# IR4427.net
KiCad netlist of a schematic drawn in EAGLE
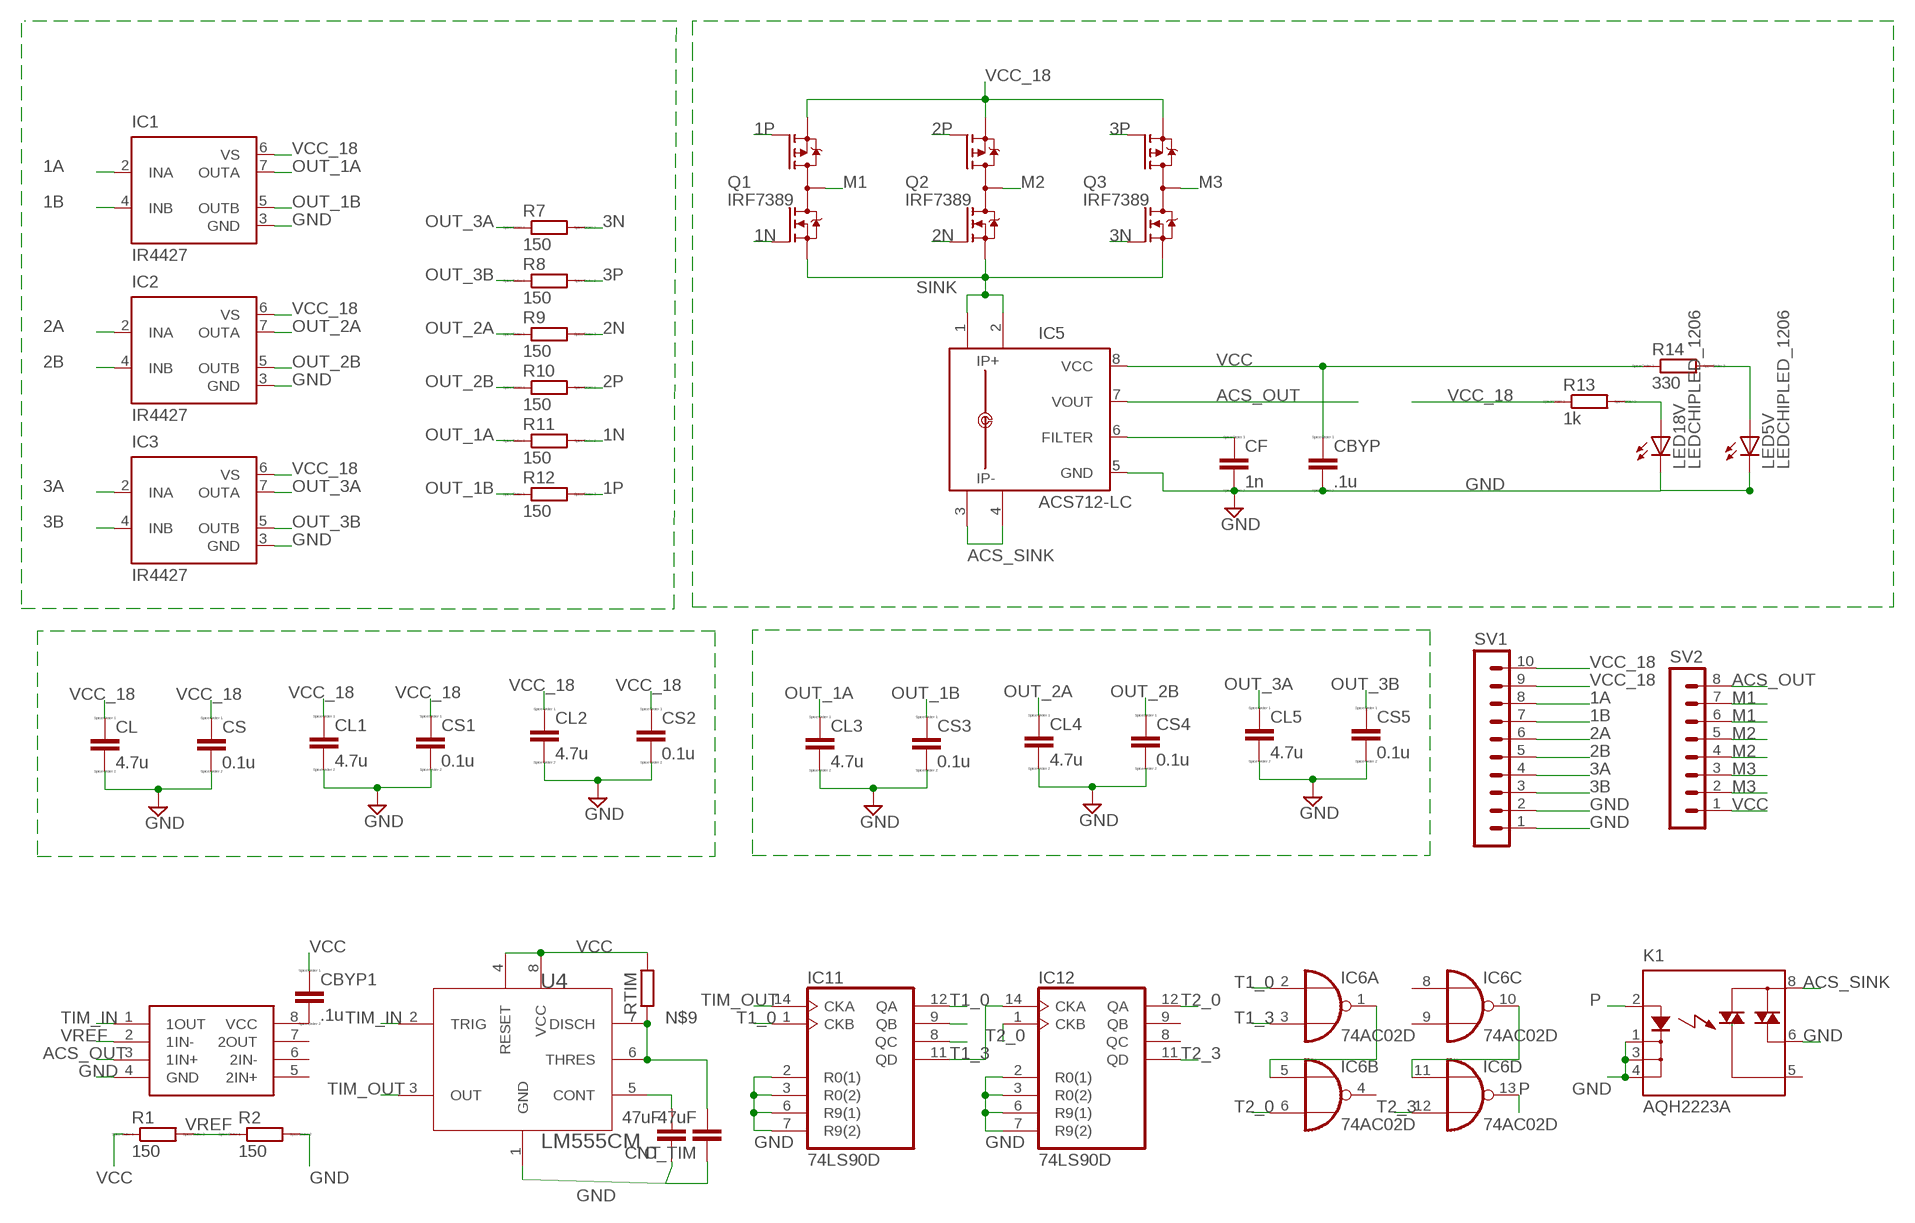
[diagram p0: schematic, sheet 1]

(export (version "E")
  (design (tool "Eeschema 10.0.6"))
  (components
    (comp (ref "CBYP")
      (value ".1u")
      (footprint "eagle-import:C1206")
      (libsource (lib "eagle-import") (part "CC1206"))
    )
    (comp (ref "CBYP1")
      (value ".1u")
      (footprint "eagle-import:C1206")
      (libsource (lib "eagle-import") (part "CC1206"))
    )
    (comp (ref "CF")
      (value "1n")
      (footprint "eagle-import:C1206")
      (libsource (lib "eagle-import") (part "CC1206"))
    )
    (comp (ref "CL")
      (value "4.7u")
      (footprint "eagle-import:C1206")
      (libsource (lib "eagle-import") (part "CC1206"))
    )
    (comp (ref "CL1")
      (value "4.7u")
      (footprint "eagle-import:C1206")
      (libsource (lib "eagle-import") (part "CC1206"))
    )
    (comp (ref "CL2")
      (value "4.7u")
      (footprint "eagle-import:C1206")
      (libsource (lib "eagle-import") (part "CC1206"))
    )
    (comp (ref "CL3")
      (value "4.7u")
      (footprint "eagle-import:C1206")
      (libsource (lib "eagle-import") (part "CC1206"))
    )
    (comp (ref "CL4")
      (value "4.7u")
      (footprint "eagle-import:C1206")
      (libsource (lib "eagle-import") (part "CC1206"))
    )
    (comp (ref "CL5")
      (value "4.7u")
      (footprint "eagle-import:C1206")
      (libsource (lib "eagle-import") (part "CC1206"))
    )
    (comp (ref "CNT")
      (value "47uF")
      (footprint "eagle-import:C1206")
      (libsource (lib "eagle-import") (part "C-EUC1206"))
    )
    (comp (ref "CS")
      (value "0.1u")
      (footprint "eagle-import:C1206")
      (libsource (lib "eagle-import") (part "CC1206"))
    )
    (comp (ref "CS1")
      (value "0.1u")
      (footprint "eagle-import:C1206")
      (libsource (lib "eagle-import") (part "CC1206"))
    )
    (comp (ref "CS2")
      (value "0.1u")
      (footprint "eagle-import:C1206")
      (libsource (lib "eagle-import") (part "CC1206"))
    )
    (comp (ref "CS3")
      (value "0.1u")
      (footprint "eagle-import:C1206")
      (libsource (lib "eagle-import") (part "CC1206"))
    )
    (comp (ref "CS4")
      (value "0.1u")
      (footprint "eagle-import:C1206")
      (libsource (lib "eagle-import") (part "CC1206"))
    )
    (comp (ref "CS5")
      (value "0.1u")
      (footprint "eagle-import:C1206")
      (libsource (lib "eagle-import") (part "CC1206"))
    )
    (comp (ref "C_TIM")
      (value "47uF")
      (footprint "eagle-import:C1206")
      (libsource (lib "eagle-import") (part "C-EUC1206"))
    )
    (comp (ref "IC1")
      (value "IR4427")
      (footprint "eagle-import:DIL08")
      (fields (field (name "MF") "INTERNATIONAL RECTIFIER(IR)"))
      (libsource (lib "eagle-import") (part "IR4427"))
    )
    (comp (ref "IC2")
      (value "IR4427")
      (footprint "eagle-import:DIL08")
      (fields (field (name "MF") "INTERNATIONAL RECTIFIER(IR)"))
      (libsource (lib "eagle-import") (part "IR4427"))
    )
    (comp (ref "IC3")
      (value "IR4427")
      (footprint "eagle-import:DIL08")
      (fields (field (name "MF") "INTERNATIONAL RECTIFIER(IR)"))
      (libsource (lib "eagle-import") (part "IR4427"))
    )
    (comp (ref "IC5")
      (value "ACS712-LC")
      (footprint "eagle-import:SOIC8")
      (libsource (lib "eagle-import") (part "ACS712-LC"))
    )
    (comp (ref "IC6")
      (value "74AC02D")
      (footprint "eagle-import:SO14")
      (libsource (lib "eagle-import") (part "7402DAC"))
    )
    (comp (ref "IC11")
      (value "74LS90D")
      (footprint "eagle-import:SO14")
      (libsource (lib "eagle-import") (part "7490DLS"))
    )
    (comp (ref "IC12")
      (value "74LS90D")
      (footprint "eagle-import:SO14")
      (libsource (lib "eagle-import") (part "7490DLS"))
    )
    (comp (ref "K1")
      (value "AQH2223A")
      (footprint "eagle-import:DIL07SMD")
      (fields (field (name "MF") "AROMAT/ MATSUSHITA"))
      (libsource (lib "eagle-import") (part "AQH223A2"))
    )
    (comp (ref "LED5V")
      (value "LEDCHIPLED_1206")
      (footprint "eagle-import:CHIPLED_1206")
      (libsource (lib "eagle-import") (part "LEDCHIPLED_1206"))
    )
    (comp (ref "LED18V")
      (value "LEDCHIPLED_1206")
      (footprint "eagle-import:CHIPLED_1206")
      (libsource (lib "eagle-import") (part "LEDCHIPLED_1206"))
    )
    (comp (ref "Q1")
      (value "IRF7389")
      (footprint "eagle-import:SO08-IRF")
      (libsource (lib "eagle-import") (part "IRF7389"))
    )
    (comp (ref "Q2")
      (value "IRF7389")
      (footprint "eagle-import:SO08-IRF")
      (libsource (lib "eagle-import") (part "IRF7389"))
    )
    (comp (ref "Q3")
      (value "IRF7389")
      (footprint "eagle-import:SO08-IRF")
      (libsource (lib "eagle-import") (part "IRF7389"))
    )
    (comp (ref "R1")
      (value "150")
      (footprint "eagle-import:R1206")
      (libsource (lib "eagle-import") (part "RR1206"))
    )
    (comp (ref "R2")
      (value "150")
      (footprint "eagle-import:R1206")
      (libsource (lib "eagle-import") (part "RR1206"))
    )
    (comp (ref "R7")
      (value "150")
      (footprint "eagle-import:R1206")
      (libsource (lib "eagle-import") (part "RR1206"))
    )
    (comp (ref "R8")
      (value "150")
      (footprint "eagle-import:R1206")
      (libsource (lib "eagle-import") (part "RR1206"))
    )
    (comp (ref "R9")
      (value "150")
      (footprint "eagle-import:R1206")
      (libsource (lib "eagle-import") (part "RR1206"))
    )
    (comp (ref "R10")
      (value "150")
      (footprint "eagle-import:R1206")
      (libsource (lib "eagle-import") (part "RR1206"))
    )
    (comp (ref "R11")
      (value "150")
      (footprint "eagle-import:R1206")
      (libsource (lib "eagle-import") (part "RR1206"))
    )
    (comp (ref "R12")
      (value "150")
      (footprint "eagle-import:R1206")
      (libsource (lib "eagle-import") (part "RR1206"))
    )
    (comp (ref "R13")
      (value "1k")
      (footprint "eagle-import:R1206")
      (libsource (lib "eagle-import") (part "RR1206"))
    )
    (comp (ref "R14")
      (value "330")
      (footprint "eagle-import:R1206")
      (libsource (lib "eagle-import") (part "RR1206"))
    )
    (comp (ref "RTIM")
      (value "R-EU_R1206")
      (footprint "eagle-import:R1206")
      (libsource (lib "eagle-import") (part "R-EU_R1206"))
    )
    (comp (ref "SV1")
      (value "MA10-1")
      (footprint "eagle-import:MA10-1")
      (libsource (lib "eagle-import") (part "MA10-1"))
    )
    (comp (ref "SV2")
      (value "MA08-1")
      (footprint "eagle-import:MA08-1")
      (libsource (lib "eagle-import") (part "MA08-1"))
    )
    (comp (ref "U1")
      (value "LM293D")
      (footprint "eagle-import:8-SOIC")
      (fields
        (field (name "DIGIKEY_PART_NUMBER") "296-9531-5-ND")
        (field (name "MANUFACTURER") "Texas Instruments")
        (field (name "CREATED_BY") "PCBLayout.com")
      )
      (libsource (lib "eagle-import") (part "LM293D"))
    )
    (comp (ref "U4")
      (value "LM555CM")
      (footprint "eagle-import:SOIC-8N")
      (fields
        (field (name "DIGI-KEY_PART") "LM555CMFS-ND")
        (field (name "MANUFACTURER") "ON Semiconductor")
        (field (name "CREATED_BY") "PCBLayout.com")
      )
      (libsource (lib "eagle-import") (part "LM555CM"))
    )
  )
  (nets
    (net (code "1") (name "/1A") (class "Default")
      (node (ref "IC1") (pin "2") (pinfunction "INA_2") (pintype "input"))
      (node (ref "SV1") (pin "8") (pinfunction "8_8") (pintype "passive"))
    )
    (net (code "2") (name "/1B") (class "Default")
      (node (ref "IC1") (pin "4") (pinfunction "INB_4") (pintype "input"))
      (node (ref "SV1") (pin "7") (pinfunction "7_7") (pintype "passive"))
    )
    (net (code "3") (name "/1N") (class "Default")
      (node (ref "Q1") (pin "2") (pinfunction "N-G_2") (pintype "passive"))
      (node (ref "R11") (pin "2") (pinfunction "2_2") (pintype "passive"))
    )
    (net (code "4") (name "/1P") (class "Default")
      (node (ref "Q1") (pin "4") (pinfunction "P-G_4") (pintype "passive"))
      (node (ref "R12") (pin "2") (pinfunction "2_2") (pintype "passive"))
    )
    (net (code "5") (name "/2A") (class "Default")
      (node (ref "IC2") (pin "2") (pinfunction "INA_2") (pintype "input"))
      (node (ref "SV1") (pin "6") (pinfunction "6_6") (pintype "passive"))
    )
    (net (code "6") (name "/2B") (class "Default")
      (node (ref "IC2") (pin "4") (pinfunction "INB_4") (pintype "input"))
      (node (ref "SV1") (pin "5") (pinfunction "5_5") (pintype "passive"))
    )
    (net (code "7") (name "/2N") (class "Default")
      (node (ref "Q2") (pin "2") (pinfunction "N-G_2") (pintype "passive"))
      (node (ref "R9") (pin "2") (pinfunction "2_2") (pintype "passive"))
    )
    (net (code "8") (name "/2P") (class "Default")
      (node (ref "Q2") (pin "4") (pinfunction "P-G_4") (pintype "passive"))
      (node (ref "R10") (pin "2") (pinfunction "2_2") (pintype "passive"))
    )
    (net (code "9") (name "/3A") (class "Default")
      (node (ref "IC3") (pin "2") (pinfunction "INA_2") (pintype "input"))
      (node (ref "SV1") (pin "4") (pinfunction "4_4") (pintype "passive"))
    )
    (net (code "10") (name "/3B") (class "Default")
      (node (ref "IC3") (pin "4") (pinfunction "INB_4") (pintype "input"))
      (node (ref "SV1") (pin "3") (pinfunction "3_3") (pintype "passive"))
    )
    (net (code "11") (name "/3N") (class "Default")
      (node (ref "Q3") (pin "2") (pinfunction "N-G_2") (pintype "passive"))
      (node (ref "R7") (pin "2") (pinfunction "2_2") (pintype "passive"))
    )
    (net (code "12") (name "/3P") (class "Default")
      (node (ref "Q3") (pin "4") (pinfunction "P-G_4") (pintype "passive"))
      (node (ref "R8") (pin "2") (pinfunction "2_2") (pintype "passive"))
    )
    (net (code "13") (name "/ACS_OUT") (class "Default")
      (node (ref "IC5") (pin "7") (pinfunction "VOUT_7") (pintype "output"))
      (node (ref "SV2") (pin "8") (pinfunction "8_8") (pintype "passive"))
      (node (ref "U1") (pin "3") (pinfunction "1IN+_3") (pintype "input"))
    )
    (net (code "14") (name "/ACS_SINK") (class "Default")
      (node (ref "IC5") (pin "3") (pinfunction "IP-_3") (pintype "passive"))
      (node (ref "IC5") (pin "4") (pinfunction "IP-1_4") (pintype "passive"))
      (node (ref "K1") (pin "8") (pinfunction "DS1_8") (pintype "passive"))
    )
    (net (code "15") (name "/M1") (class "Default")
      (node (ref "Q1") (pin "5") (pinfunction "D_5") (pintype "passive"))
      (node (ref "Q1") (pin "6") (pinfunction "D_6") (pintype "passive"))
      (node (ref "Q1") (pin "7") (pinfunction "D_7") (pintype "passive"))
      (node (ref "Q1") (pin "8") (pinfunction "D_8") (pintype "passive"))
      (node (ref "SV2") (pin "6") (pinfunction "6_6") (pintype "passive"))
      (node (ref "SV2") (pin "7") (pinfunction "7_7") (pintype "passive"))
    )
    (net (code "16") (name "/M2") (class "Default")
      (node (ref "Q2") (pin "5") (pinfunction "D_5") (pintype "passive"))
      (node (ref "Q2") (pin "6") (pinfunction "D_6") (pintype "passive"))
      (node (ref "Q2") (pin "7") (pinfunction "D_7") (pintype "passive"))
      (node (ref "Q2") (pin "8") (pinfunction "D_8") (pintype "passive"))
      (node (ref "SV2") (pin "4") (pinfunction "4_4") (pintype "passive"))
      (node (ref "SV2") (pin "5") (pinfunction "5_5") (pintype "passive"))
    )
    (net (code "17") (name "/M3") (class "Default")
      (node (ref "Q3") (pin "5") (pinfunction "D_5") (pintype "passive"))
      (node (ref "Q3") (pin "6") (pinfunction "D_6") (pintype "passive"))
      (node (ref "Q3") (pin "7") (pinfunction "D_7") (pintype "passive"))
      (node (ref "Q3") (pin "8") (pinfunction "D_8") (pintype "passive"))
      (node (ref "SV2") (pin "2") (pinfunction "2_2") (pintype "passive"))
      (node (ref "SV2") (pin "3") (pinfunction "3_3") (pintype "passive"))
    )
    (net (code "18") (name "/N$9") (class "Default")
      (node (ref "RTIM") (pin "1") (pinfunction "1_1") (pintype "passive"))
      (node (ref "U4") (pin "7") (pinfunction "DISCH_7") (pintype "output"))
    )
    (net (code "19") (name "/OUT_1A") (class "Default")
      (node (ref "CL3") (pin "1") (pinfunction "1_1") (pintype "passive"))
      (node (ref "IC1") (pin "7") (pinfunction "OUTA_7") (pintype "output"))
      (node (ref "R11") (pin "1") (pinfunction "1_1") (pintype "passive"))
    )
    (net (code "20") (name "/OUT_1B") (class "Default")
      (node (ref "CS3") (pin "1") (pinfunction "1_1") (pintype "passive"))
      (node (ref "IC1") (pin "5") (pinfunction "OUTB_5") (pintype "output"))
      (node (ref "R12") (pin "1") (pinfunction "1_1") (pintype "passive"))
    )
    (net (code "21") (name "/OUT_2A") (class "Default")
      (node (ref "CL4") (pin "1") (pinfunction "1_1") (pintype "passive"))
      (node (ref "IC2") (pin "7") (pinfunction "OUTA_7") (pintype "output"))
      (node (ref "R9") (pin "1") (pinfunction "1_1") (pintype "passive"))
    )
    (net (code "22") (name "/OUT_2B") (class "Default")
      (node (ref "CS4") (pin "1") (pinfunction "1_1") (pintype "passive"))
      (node (ref "IC2") (pin "5") (pinfunction "OUTB_5") (pintype "output"))
      (node (ref "R10") (pin "1") (pinfunction "1_1") (pintype "passive"))
    )
    (net (code "23") (name "/OUT_3A") (class "Default")
      (node (ref "CL5") (pin "1") (pinfunction "1_1") (pintype "passive"))
      (node (ref "IC3") (pin "7") (pinfunction "OUTA_7") (pintype "output"))
      (node (ref "R7") (pin "1") (pinfunction "1_1") (pintype "passive"))
    )
    (net (code "24") (name "/OUT_3B") (class "Default")
      (node (ref "CS5") (pin "1") (pinfunction "1_1") (pintype "passive"))
      (node (ref "IC3") (pin "5") (pinfunction "OUTB_5") (pintype "output"))
      (node (ref "R8") (pin "1") (pinfunction "1_1") (pintype "passive"))
    )
    (net (code "25") (name "/P") (class "Default")
      (node (ref "IC6") (pin "13") (pinfunction "O_13") (pintype "output"))
      (node (ref "K1") (pin "2") (pinfunction "A_2") (pintype "passive"))
    )
    (net (code "26") (name "/SINK") (class "Default")
      (node (ref "IC5") (pin "1") (pinfunction "IP+_1") (pintype "passive"))
      (node (ref "IC5") (pin "2") (pinfunction "IP+1_2") (pintype "passive"))
      (node (ref "Q1") (pin "1") (pinfunction "N-S_1") (pintype "passive"))
      (node (ref "Q2") (pin "1") (pinfunction "N-S_1") (pintype "passive"))
      (node (ref "Q3") (pin "1") (pinfunction "N-S_1") (pintype "passive"))
    )
    (net (code "27") (name "/T1_0") (class "Default")
      (node (ref "IC11") (pin "1") (pinfunction "CKB_1") (pintype "input"))
      (node (ref "IC11") (pin "12") (pinfunction "QA_12") (pintype "output"))
      (node (ref "IC6") (pin "2") (pinfunction "I0_2") (pintype "input"))
    )
    (net (code "28") (name "/T1_3") (class "Default")
      (node (ref "IC11") (pin "11") (pinfunction "QD_11") (pintype "output"))
      (node (ref "IC12") (pin "14") (pinfunction "CKA_14") (pintype "input"))
      (node (ref "IC6") (pin "3") (pinfunction "I1_3") (pintype "input"))
    )
    (net (code "29") (name "/T2_0") (class "Default")
      (node (ref "IC12") (pin "1") (pinfunction "CKB_1") (pintype "input"))
      (node (ref "IC12") (pin "12") (pinfunction "QA_12") (pintype "output"))
      (node (ref "IC6") (pin "6") (pinfunction "I1_6") (pintype "input"))
    )
    (net (code "30") (name "/T2_3") (class "Default")
      (node (ref "IC12") (pin "11") (pinfunction "QD_11") (pintype "output"))
      (node (ref "IC6") (pin "12") (pinfunction "I1_12") (pintype "input"))
    )
    (net (code "31") (name "/TIM_IN") (class "Default")
      (node (ref "U1") (pin "1") (pinfunction "1OUT_1") (pintype "output"))
      (node (ref "U4") (pin "2") (pinfunction "TRIG_2") (pintype "input"))
    )
    (net (code "32") (name "/TIM_OUT") (class "Default")
      (node (ref "IC11") (pin "14") (pinfunction "CKA_14") (pintype "input"))
      (node (ref "U4") (pin "3") (pinfunction "OUT_3") (pintype "output"))
    )
    (net (code "33") (name "/VCC") (class "Default")
      (node (ref "CBYP") (pin "1") (pinfunction "1_1") (pintype "passive"))
      (node (ref "CBYP1") (pin "1") (pinfunction "1_1") (pintype "passive"))
      (node (ref "IC5") (pin "8") (pinfunction "VCC_8") (pintype "power_in"))
      (node (ref "R1") (pin "1") (pinfunction "1_1") (pintype "passive"))
      (node (ref "R14") (pin "1") (pinfunction "1_1") (pintype "passive"))
      (node (ref "RTIM") (pin "2") (pinfunction "2_2") (pintype "passive"))
      (node (ref "SV2") (pin "1") (pinfunction "1_1") (pintype "passive"))
      (node (ref "U4") (pin "4") (pinfunction "RESET_4") (pintype "input"))
      (node (ref "U4") (pin "8") (pinfunction "VCC_8") (pintype "power_in"))
    )
    (net (code "34") (name "/VCC_18") (class "Default")
      (node (ref "CL") (pin "1") (pinfunction "1_1") (pintype "passive"))
      (node (ref "CL1") (pin "1") (pinfunction "1_1") (pintype "passive"))
      (node (ref "CL2") (pin "1") (pinfunction "1_1") (pintype "passive"))
      (node (ref "CS") (pin "1") (pinfunction "1_1") (pintype "passive"))
      (node (ref "CS1") (pin "1") (pinfunction "1_1") (pintype "passive"))
      (node (ref "CS2") (pin "1") (pinfunction "1_1") (pintype "passive"))
      (node (ref "IC1") (pin "6") (pinfunction "VS_6") (pintype "power_in"))
      (node (ref "IC2") (pin "6") (pinfunction "VS_6") (pintype "power_in"))
      (node (ref "IC3") (pin "6") (pinfunction "VS_6") (pintype "power_in"))
      (node (ref "Q1") (pin "3") (pinfunction "P-S_3") (pintype "passive"))
      (node (ref "Q2") (pin "3") (pinfunction "P-S_3") (pintype "passive"))
      (node (ref "Q3") (pin "3") (pinfunction "P-S_3") (pintype "passive"))
      (node (ref "R13") (pin "1") (pinfunction "1_1") (pintype "passive"))
      (node (ref "SV1") (pin "10") (pinfunction "10_10") (pintype "passive"))
      (node (ref "SV1") (pin "9") (pinfunction "9_9") (pintype "passive"))
    )
    (net (code "35") (name "/VREF") (class "Default")
      (node (ref "R1") (pin "2") (pinfunction "2_2") (pintype "passive"))
      (node (ref "R2") (pin "1") (pinfunction "1_1") (pintype "passive"))
      (node (ref "U1") (pin "2") (pinfunction "1IN-_2") (pintype "input"))
    )
    (net (code "36") (name "GND") (class "Default")
      (node (ref "CBYP") (pin "2") (pinfunction "2_2") (pintype "passive"))
      (node (ref "CF") (pin "2") (pinfunction "2_2") (pintype "passive"))
      (node (ref "CL") (pin "2") (pinfunction "2_2") (pintype "passive"))
      (node (ref "CL1") (pin "2") (pinfunction "2_2") (pintype "passive"))
      (node (ref "CL2") (pin "2") (pinfunction "2_2") (pintype "passive"))
      (node (ref "CL3") (pin "2") (pinfunction "2_2") (pintype "passive"))
      (node (ref "CL4") (pin "2") (pinfunction "2_2") (pintype "passive"))
      (node (ref "CL5") (pin "2") (pinfunction "2_2") (pintype "passive"))
      (node (ref "CNT") (pin "1") (pinfunction "1_1") (pintype "passive"))
      (node (ref "CS") (pin "2") (pinfunction "2_2") (pintype "passive"))
      (node (ref "CS1") (pin "2") (pinfunction "2_2") (pintype "passive"))
      (node (ref "CS2") (pin "2") (pinfunction "2_2") (pintype "passive"))
      (node (ref "CS3") (pin "2") (pinfunction "2_2") (pintype "passive"))
      (node (ref "CS4") (pin "2") (pinfunction "2_2") (pintype "passive"))
      (node (ref "CS5") (pin "2") (pinfunction "2_2") (pintype "passive"))
      (node (ref "C_TIM") (pin "1") (pinfunction "1_1") (pintype "passive"))
      (node (ref "IC1") (pin "3") (pinfunction "GND_3") (pintype "power_in"))
      (node (ref "IC11") (pin "2") (pinfunction "R0(1)_2") (pintype "input"))
      (node (ref "IC11") (pin "3") (pinfunction "R0(2)_3") (pintype "input"))
      (node (ref "IC11") (pin "6") (pinfunction "R9(1)_6") (pintype "input"))
      (node (ref "IC11") (pin "7") (pinfunction "R9(2)_7") (pintype "input"))
      (node (ref "IC12") (pin "2") (pinfunction "R0(1)_2") (pintype "input"))
      (node (ref "IC12") (pin "3") (pinfunction "R0(2)_3") (pintype "input"))
      (node (ref "IC12") (pin "6") (pinfunction "R9(1)_6") (pintype "input"))
      (node (ref "IC12") (pin "7") (pinfunction "R9(2)_7") (pintype "input"))
      (node (ref "IC2") (pin "3") (pinfunction "GND_3") (pintype "power_in"))
      (node (ref "IC3") (pin "3") (pinfunction "GND_3") (pintype "power_in"))
      (node (ref "IC5") (pin "5") (pinfunction "GND_5") (pintype "power_in"))
      (node (ref "K1") (pin "1") (pinfunction "K_1") (pintype "passive"))
      (node (ref "K1") (pin "3") (pinfunction "K1_3") (pintype "passive"))
      (node (ref "K1") (pin "4") (pinfunction "K2_4") (pintype "passive"))
      (node (ref "K1") (pin "6") (pinfunction "DS3_6") (pintype "passive"))
      (node (ref "LED18V") (pin "C") (pinfunction "C_C") (pintype "passive"))
      (node (ref "LED5V") (pin "C") (pinfunction "C_C") (pintype "passive"))
      (node (ref "R2") (pin "2") (pinfunction "2_2") (pintype "passive"))
      (node (ref "SV1") (pin "1") (pinfunction "1_1") (pintype "passive"))
      (node (ref "SV1") (pin "2") (pinfunction "2_2") (pintype "passive"))
      (node (ref "U1") (pin "4") (pinfunction "GND_4") (pintype "power_in"))
      (node (ref "U4") (pin "1") (pinfunction "GND_1") (pintype "power_in"))
    )
    (net (code "37") (name "Net-(IC5-FILTER)") (class "Default")
      (node (ref "CF") (pin "1") (pinfunction "1_1") (pintype "passive"))
      (node (ref "IC5") (pin "6") (pinfunction "FILTER_6") (pintype "bidirectional"))
    )
    (net (code "38") (name "Net-(IC6A-O)") (class "Default")
      (node (ref "IC6") (pin "1") (pinfunction "O_1") (pintype "output"))
      (node (ref "IC6") (pin "5") (pinfunction "I0_5") (pintype "input"))
    )
    (net (code "39") (name "Net-(IC6C-O)") (class "Default")
      (node (ref "IC6") (pin "10") (pinfunction "O_10") (pintype "output"))
      (node (ref "IC6") (pin "11") (pinfunction "I0_11") (pintype "input"))
    )
    (net (code "40") (name "Net-(LED5V-PadA)") (class "Default")
      (node (ref "LED5V") (pin "A") (pinfunction "A_A") (pintype "passive"))
      (node (ref "R14") (pin "2") (pinfunction "2_2") (pintype "passive"))
    )
    (net (code "41") (name "Net-(LED18V-PadA)") (class "Default")
      (node (ref "LED18V") (pin "A") (pinfunction "A_A") (pintype "passive"))
      (node (ref "R13") (pin "2") (pinfunction "2_2") (pintype "passive"))
    )
    (net (code "42") (name "Net-(U1-VCC)") (class "Default")
      (node (ref "CBYP1") (pin "2") (pinfunction "2_2") (pintype "passive"))
      (node (ref "U1") (pin "8") (pinfunction "VCC_8") (pintype "power_in"))
    )
    (net (code "43") (name "Net-(U4-CONT)") (class "Default")
      (node (ref "CNT") (pin "2") (pinfunction "2_2") (pintype "passive"))
      (node (ref "U4") (pin "5") (pinfunction "CONT_5") (pintype "bidirectional"))
    )
    (net (code "44") (name "Net-(U4-THRES)") (class "Default")
      (node (ref "C_TIM") (pin "2") (pinfunction "2_2") (pintype "passive"))
      (node (ref "U4") (pin "6") (pinfunction "THRES_6") (pintype "input"))
    )
    (net (code "45") (name "unconnected-(IC6B-O-Pad4)") (class "Default")
      (node (ref "IC6") (pin "4") (pinfunction "O_4") (pintype "output"))
    )
    (net (code "46") (name "unconnected-(IC6C-I0-Pad8)") (class "Default")
      (node (ref "IC6") (pin "8") (pinfunction "I0_8") (pintype "input"))
    )
    (net (code "47") (name "unconnected-(IC6C-I1-Pad9)") (class "Default")
      (node (ref "IC6") (pin "9") (pinfunction "I1_9") (pintype "input"))
    )
    (net (code "48") (name "unconnected-(IC11A-QB-Pad9)") (class "Default")
      (node (ref "IC11") (pin "9") (pinfunction "QB_9") (pintype "output"))
    )
    (net (code "49") (name "unconnected-(IC11A-QC-Pad8)") (class "Default")
      (node (ref "IC11") (pin "8") (pinfunction "QC_8") (pintype "output"))
    )
    (net (code "50") (name "unconnected-(IC12A-QB-Pad9)") (class "Default")
      (node (ref "IC12") (pin "9") (pinfunction "QB_9") (pintype "output"))
    )
    (net (code "51") (name "unconnected-(IC12A-QC-Pad8)") (class "Default")
      (node (ref "IC12") (pin "8") (pinfunction "QC_8") (pintype "output"))
    )
    (net (code "52") (name "unconnected-(K1-DS2-Pad5)") (class "Default")
      (node (ref "K1") (pin "5") (pinfunction "DS2_5") (pintype "passive"))
    )
    (net (code "53") (name "unconnected-(U1-2IN+-Pad5)") (class "Default")
      (node (ref "U1") (pin "5") (pinfunction "2IN+_5") (pintype "input"))
    )
    (net (code "54") (name "unconnected-(U1-2IN--Pad6)") (class "Default")
      (node (ref "U1") (pin "6") (pinfunction "2IN-_6") (pintype "input"))
    )
    (net (code "55") (name "unconnected-(U1-2OUT-Pad7)") (class "Default")
      (node (ref "U1") (pin "7") (pinfunction "2OUT_7") (pintype "output"))
    )
  )
)
